# thesis.net
KiCad netlist of a schematic drawn in EAGLE
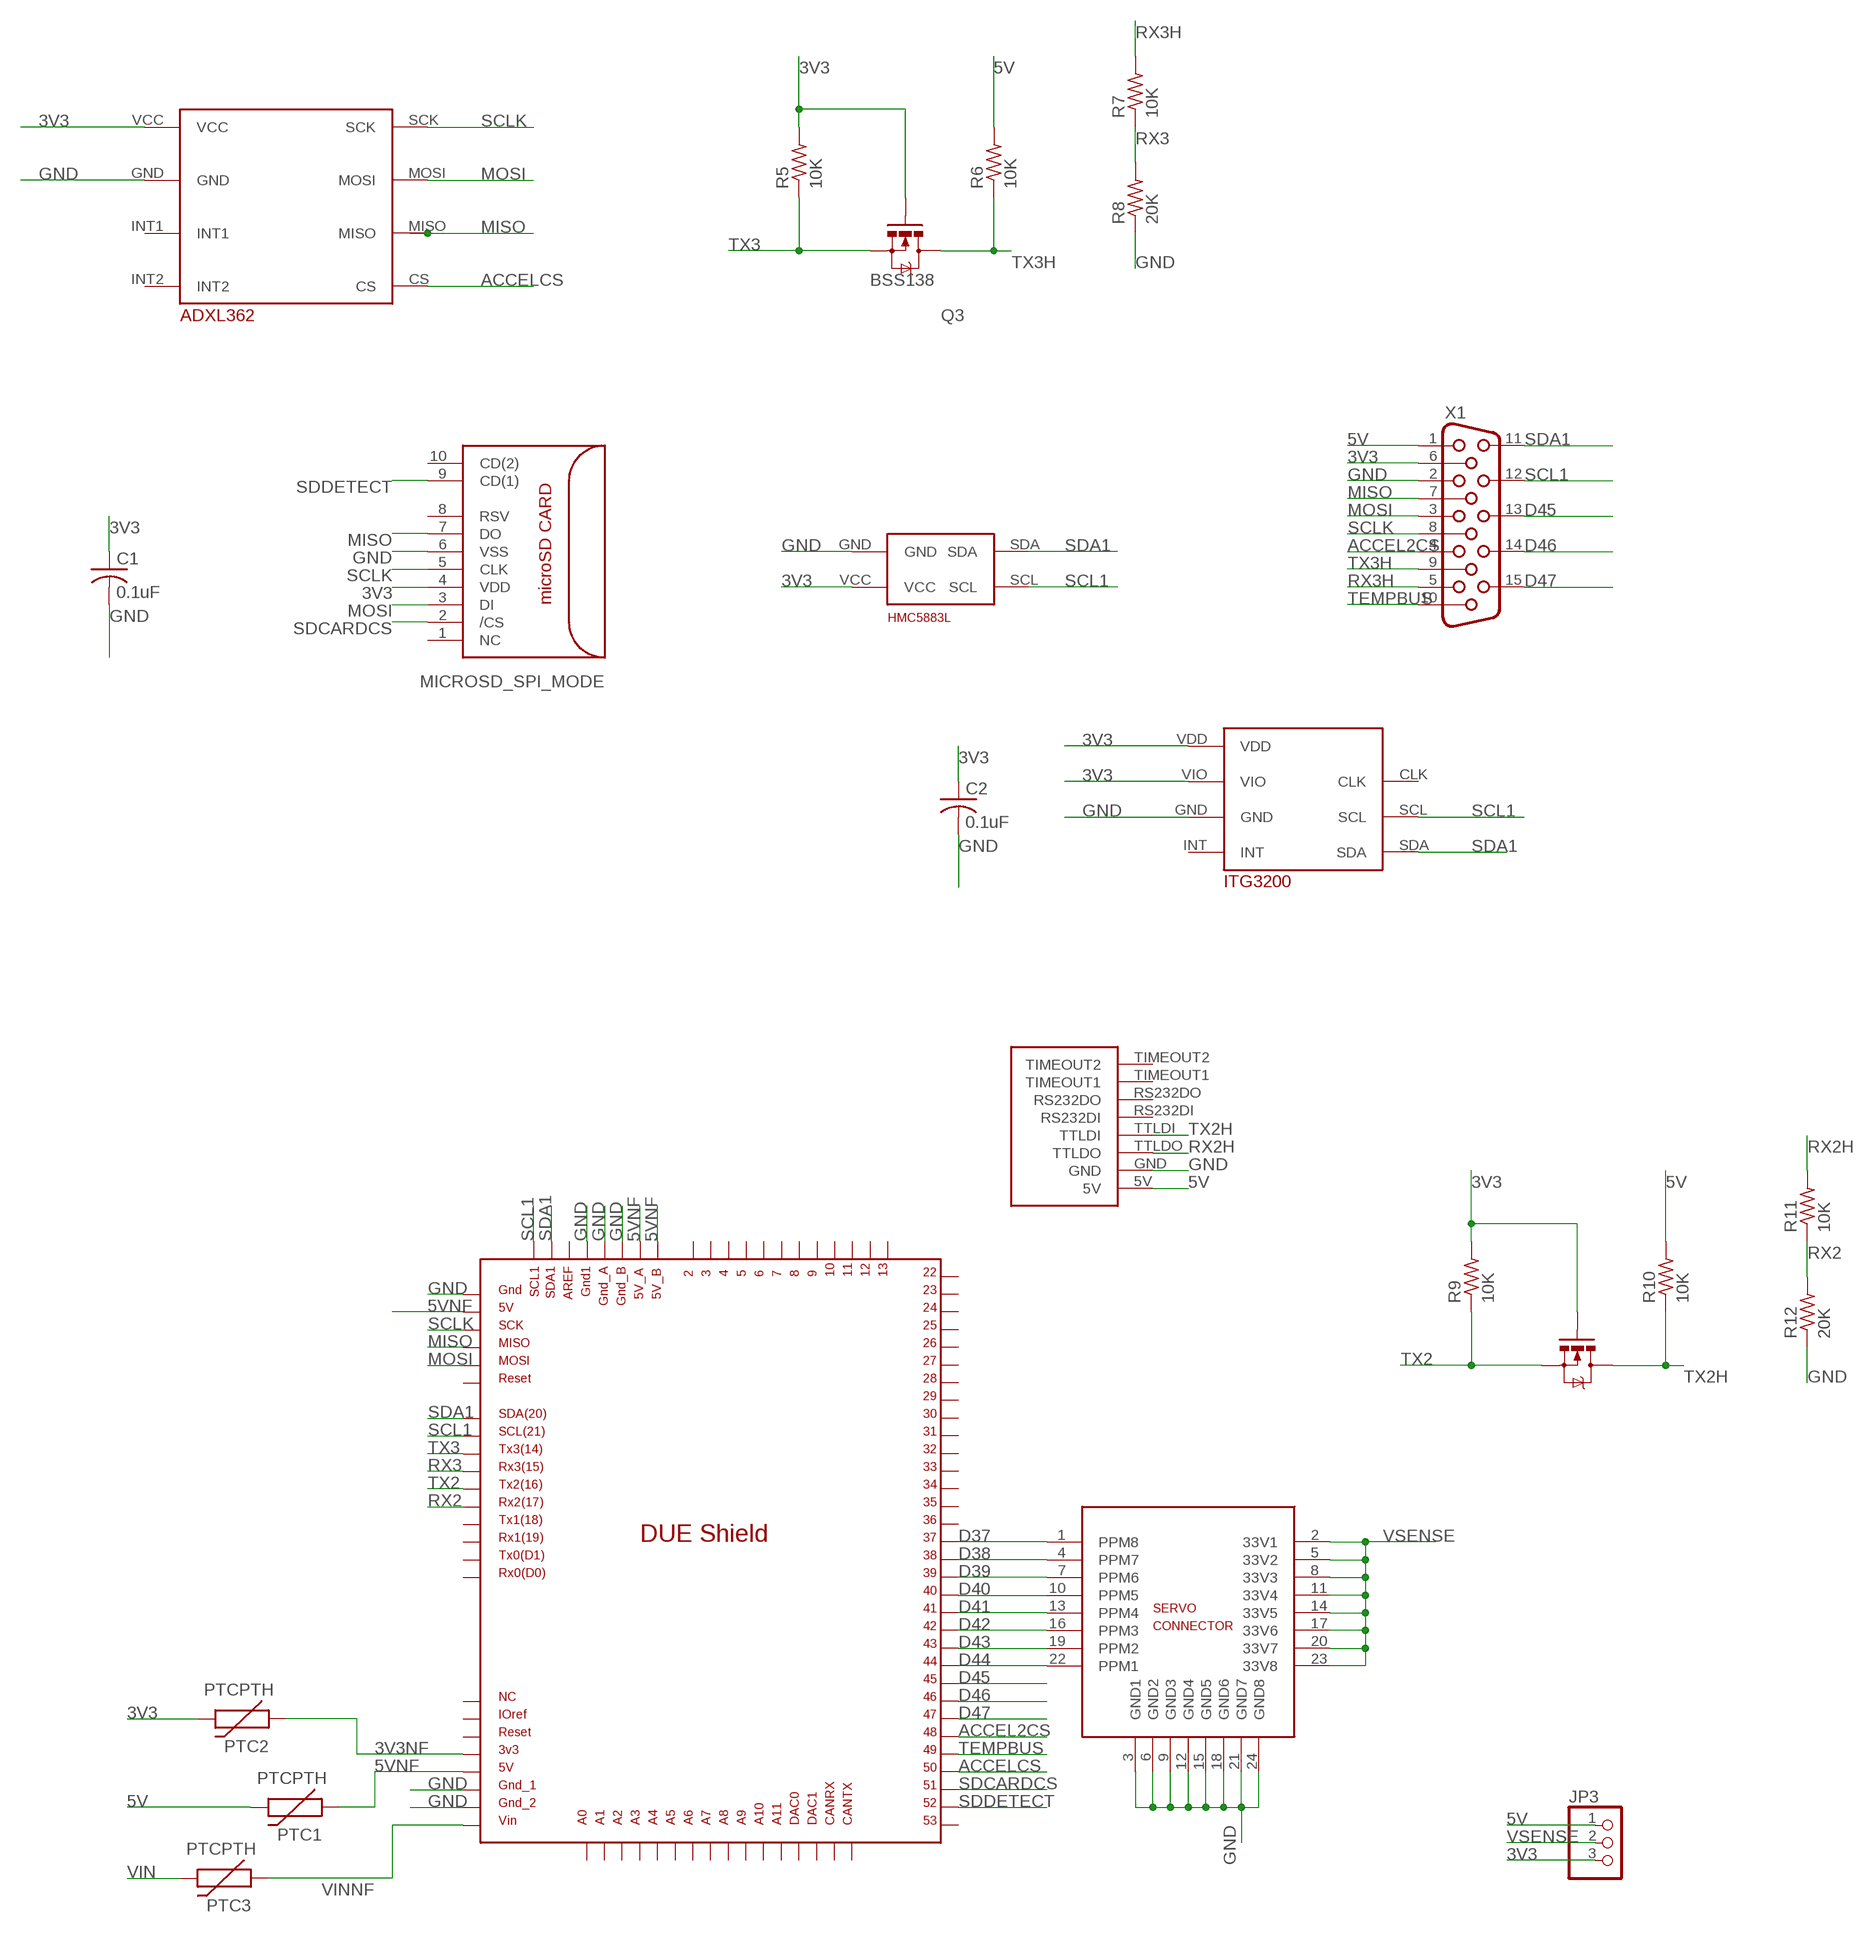
[diagram p0: schematic, sheet 1]

(export (version "E")
  (design (tool "Eeschema 10.0.6"))
  (components
    (comp (ref "C1")
      (value "0.1uF")
      (footprint "eagle-import:C0603")
      (libsource (lib "eagle-import") (part "C-USC0603"))
    )
    (comp (ref "C2")
      (value "0.1uF")
      (footprint "eagle-import:C0603")
      (libsource (lib "eagle-import") (part "C-USC0603"))
    )
    (comp (ref "JP3")
      (value "PINHD-1X3")
      (footprint "eagle-import:1X03")
      (libsource (lib "eagle-import") (part "PINHD-1X3"))
    )
    (comp (ref "PTC1")
      (value "PTCPTH")
      (footprint "eagle-import:PTC")
      (libsource (lib "eagle-import") (part "PTCPTH"))
    )
    (comp (ref "PTC2")
      (value "PTCPTH")
      (footprint "eagle-import:PTC")
      (libsource (lib "eagle-import") (part "PTCPTH"))
    )
    (comp (ref "PTC3")
      (value "PTCPTH")
      (footprint "eagle-import:PTC")
      (libsource (lib "eagle-import") (part "PTCPTH"))
    )
    (comp (ref "Q1")
      (value "BSS138")
      (footprint "eagle-import:SOT23")
      (libsource (lib "eagle-import") (part "MOSFET-NCHANNELBSS123LT1G"))
    )
    (comp (ref "Q3")
      (value "BSS138")
      (footprint "eagle-import:SOT23")
      (libsource (lib "eagle-import") (part "MOSFET-NCHANNELBSS123LT1G"))
    )
    (comp (ref "R5")
      (value "10K")
      (footprint "eagle-import:R0603")
      (libsource (lib "eagle-import") (part "R-US_R0603"))
    )
    (comp (ref "R6")
      (value "10K")
      (footprint "eagle-import:R0603")
      (libsource (lib "eagle-import") (part "R-US_R0603"))
    )
    (comp (ref "R7")
      (value "10K")
      (footprint "eagle-import:R0603")
      (libsource (lib "eagle-import") (part "R-US_R0603"))
    )
    (comp (ref "R8")
      (value "20K")
      (footprint "eagle-import:R0603")
      (libsource (lib "eagle-import") (part "R-US_R0603"))
    )
    (comp (ref "R9")
      (value "10K")
      (footprint "eagle-import:R0603")
      (libsource (lib "eagle-import") (part "R-US_R0603"))
    )
    (comp (ref "R10")
      (value "10K")
      (footprint "eagle-import:R0603")
      (libsource (lib "eagle-import") (part "R-US_R0603"))
    )
    (comp (ref "R11")
      (value "10K")
      (footprint "eagle-import:R0603")
      (libsource (lib "eagle-import") (part "R-US_R0603"))
    )
    (comp (ref "R12")
      (value "20K")
      (footprint "eagle-import:R0603")
      (libsource (lib "eagle-import") (part "R-US_R0603"))
    )
    (comp (ref "U$1")
      (value "DUE(NORMAL)")
      (footprint "eagle-import:DUE(NORMAL)")
      (libsource (lib "eagle-import") (part "DUE(NORMAL)"))
    )
    (comp (ref "U$2")
      (value "MICROSD_SPI_MODE")
      (footprint "eagle-import:MICRO_SD_CONNECTOR")
      (libsource (lib "eagle-import") (part "MICROSD_SPI_MODE"))
    )
    (comp (ref "U$4")
      (value "HMC5883L")
      (footprint "eagle-import:HMC5883L")
      (libsource (lib "eagle-import") (part "HMC5883L"))
    )
    (comp (ref "U$5")
      (value "HEADER-3X8SERVO")
      (footprint "eagle-import:3X8RA")
      (libsource (lib "eagle-import") (part "HEADER-3X8SERVO"))
    )
    (comp (ref "U$6")
      (value "UBLOXLEA6TBOB")
      (footprint "eagle-import:UBLOXLEA6TBOB")
      (libsource (lib "eagle-import") (part "UBLOXLEA6TBOB"))
    )
    (comp (ref "U$7")
      (value "ITG3200")
      (footprint "eagle-import:ITG3200")
      (libsource (lib "eagle-import") (part "ITG3200"))
    )
    (comp (ref "U$8")
      (value "ADXL362")
      (footprint "eagle-import:ADXL362")
      (libsource (lib "eagle-import") (part "ADXL362"))
    )
    (comp (ref "X1")
      (value "HF15V")
      (footprint "eagle-import:HDF15V")
      (libsource (lib "eagle-import") (part "HF15V"))
    )
  )
  (nets
    (net (code "1") (name "/3V3") (class "Default")
      (node (ref "C1") (pin "1") (pinfunction "1_1") (pintype "passive"))
      (node (ref "C2") (pin "1") (pinfunction "1_1") (pintype "passive"))
      (node (ref "JP3") (pin "3") (pinfunction "3_3") (pintype "passive"))
      (node (ref "PTC2") (pin "P$2") (pinfunction "2_P$2") (pintype "bidirectional"))
      (node (ref "Q1") (pin "1") (pinfunction "G_1") (pintype "passive"))
      (node (ref "Q3") (pin "1") (pinfunction "G_1") (pintype "passive"))
      (node (ref "R5") (pin "2") (pinfunction "2_2") (pintype "passive"))
      (node (ref "R9") (pin "2") (pinfunction "2_2") (pintype "passive"))
      (node (ref "U$2") (pin "4") (pinfunction "VDD_4") (pintype "bidirectional"))
      (node (ref "U$4") (pin "VCC") (pinfunction "VCC_VCC") (pintype "bidirectional"))
      (node (ref "U$7") (pin "VDD") (pinfunction "VDD_VDD") (pintype "bidirectional"))
      (node (ref "U$7") (pin "VIO") (pinfunction "VIO_VIO") (pintype "bidirectional"))
      (node (ref "U$8") (pin "VCC") (pinfunction "VCC_VCC") (pintype "bidirectional"))
      (node (ref "X1") (pin "6") (pinfunction "6_6") (pintype "passive"))
    )
    (net (code "2") (name "/3V3NF") (class "Default")
      (node (ref "PTC2") (pin "P$1") (pinfunction "1_P$1") (pintype "bidirectional"))
      (node (ref "U$1") (pin "3V3") (pinfunction "3V3_3V3") (pintype "bidirectional"))
    )
    (net (code "3") (name "/5V") (class "Default")
      (node (ref "JP3") (pin "1") (pinfunction "1_1") (pintype "passive"))
      (node (ref "PTC1") (pin "P$2") (pinfunction "2_P$2") (pintype "bidirectional"))
      (node (ref "R10") (pin "2") (pinfunction "2_2") (pintype "passive"))
      (node (ref "R6") (pin "2") (pinfunction "2_2") (pintype "passive"))
      (node (ref "U$6") (pin "5V") (pinfunction "5V_5V") (pintype "bidirectional"))
      (node (ref "X1") (pin "1") (pinfunction "1_1") (pintype "passive"))
    )
    (net (code "4") (name "/5VNF") (class "Default")
      (node (ref "PTC1") (pin "P$1") (pinfunction "1_P$1") (pintype "bidirectional"))
      (node (ref "U$1") (pin "5V") (pinfunction "5V_5V") (pintype "bidirectional"))
      (node (ref "U$1") (pin "5V_A") (pinfunction "5V_A_5V_A") (pintype "bidirectional"))
      (node (ref "U$1") (pin "5V_B") (pinfunction "5V_B_5V_B") (pintype "bidirectional"))
      (node (ref "U$1") (pin "GND_ICSP") (pinfunction "GND_ICSP_GND_ICSP") (pintype "bidirectional"))
    )
    (net (code "5") (name "/ACCEL2CS") (class "Default")
      (node (ref "U$1") (pin "48") (pinfunction "48_48") (pintype "bidirectional"))
      (node (ref "X1") (pin "4") (pinfunction "4_4") (pintype "passive"))
    )
    (net (code "6") (name "/ACCELCS") (class "Default")
      (node (ref "U$1") (pin "50") (pinfunction "50_50") (pintype "bidirectional"))
      (node (ref "U$8") (pin "CS") (pinfunction "CS_CS") (pintype "bidirectional"))
    )
    (net (code "7") (name "/D37") (class "Default")
      (node (ref "U$1") (pin "37") (pinfunction "37_37") (pintype "bidirectional"))
      (node (ref "U$5") (pin "1") (pinfunction "PPM8_1") (pintype "bidirectional"))
    )
    (net (code "8") (name "/D38") (class "Default")
      (node (ref "U$1") (pin "38") (pinfunction "38_38") (pintype "bidirectional"))
      (node (ref "U$5") (pin "4") (pinfunction "PPM7_4") (pintype "bidirectional"))
    )
    (net (code "9") (name "/D39") (class "Default")
      (node (ref "U$1") (pin "39") (pinfunction "39_39") (pintype "bidirectional"))
      (node (ref "U$5") (pin "7") (pinfunction "PPM6_7") (pintype "bidirectional"))
    )
    (net (code "10") (name "/D40") (class "Default")
      (node (ref "U$1") (pin "40") (pinfunction "40_40") (pintype "bidirectional"))
      (node (ref "U$5") (pin "10") (pinfunction "PPM5_10") (pintype "bidirectional"))
    )
    (net (code "11") (name "/D41") (class "Default")
      (node (ref "U$1") (pin "41") (pinfunction "41_41") (pintype "bidirectional"))
      (node (ref "U$5") (pin "13") (pinfunction "PPM4_13") (pintype "bidirectional"))
    )
    (net (code "12") (name "/D42") (class "Default")
      (node (ref "U$1") (pin "42") (pinfunction "42_42") (pintype "bidirectional"))
      (node (ref "U$5") (pin "16") (pinfunction "PPM3_16") (pintype "bidirectional"))
    )
    (net (code "13") (name "/D43") (class "Default")
      (node (ref "U$1") (pin "43") (pinfunction "43_43") (pintype "bidirectional"))
      (node (ref "U$5") (pin "19") (pinfunction "PPM2_19") (pintype "bidirectional"))
    )
    (net (code "14") (name "/D44") (class "Default")
      (node (ref "U$1") (pin "44") (pinfunction "44_44") (pintype "bidirectional"))
      (node (ref "U$5") (pin "22") (pinfunction "PPM1_22") (pintype "bidirectional"))
    )
    (net (code "15") (name "/D45") (class "Default")
      (node (ref "U$1") (pin "45") (pinfunction "45_45") (pintype "bidirectional"))
      (node (ref "X1") (pin "13") (pinfunction "13_13") (pintype "passive"))
    )
    (net (code "16") (name "/D46") (class "Default")
      (node (ref "U$1") (pin "46") (pinfunction "46_46") (pintype "bidirectional"))
      (node (ref "X1") (pin "14") (pinfunction "14_14") (pintype "passive"))
    )
    (net (code "17") (name "/D47") (class "Default")
      (node (ref "U$1") (pin "47") (pinfunction "47_47") (pintype "bidirectional"))
      (node (ref "X1") (pin "15") (pinfunction "15_15") (pintype "passive"))
    )
    (net (code "18") (name "/GND") (class "Default")
      (node (ref "C1") (pin "2") (pinfunction "2_2") (pintype "passive"))
      (node (ref "C2") (pin "2") (pinfunction "2_2") (pintype "passive"))
      (node (ref "R12") (pin "1") (pinfunction "1_1") (pintype "passive"))
      (node (ref "R8") (pin "1") (pinfunction "1_1") (pintype "passive"))
      (node (ref "U$1") (pin "5V_ICSP") (pinfunction "5V_ICSP_5V_ICSP") (pintype "bidirectional"))
      (node (ref "U$1") (pin "GND1") (pinfunction "GND1_GND1") (pintype "bidirectional"))
      (node (ref "U$1") (pin "GND_1") (pinfunction "GND_1_GND_1") (pintype "bidirectional"))
      (node (ref "U$1") (pin "GND_2") (pinfunction "GND_2_GND_2") (pintype "bidirectional"))
      (node (ref "U$1") (pin "GND_A") (pinfunction "GND_A_GND_A") (pintype "bidirectional"))
      (node (ref "U$1") (pin "GND_B") (pinfunction "GND_B_GND_B") (pintype "bidirectional"))
      (node (ref "U$2") (pin "6") (pinfunction "VSS_6") (pintype "bidirectional"))
      (node (ref "U$4") (pin "GND") (pinfunction "GND_GND") (pintype "bidirectional"))
      (node (ref "U$5") (pin "12") (pinfunction "GND4_12") (pintype "bidirectional"))
      (node (ref "U$5") (pin "15") (pinfunction "GND5_15") (pintype "bidirectional"))
      (node (ref "U$5") (pin "18") (pinfunction "GND6_18") (pintype "bidirectional"))
      (node (ref "U$5") (pin "21") (pinfunction "GND7_21") (pintype "bidirectional"))
      (node (ref "U$5") (pin "24") (pinfunction "GND8_24") (pintype "bidirectional"))
      (node (ref "U$5") (pin "3") (pinfunction "GND1_3") (pintype "bidirectional"))
      (node (ref "U$5") (pin "6") (pinfunction "GND2_6") (pintype "bidirectional"))
      (node (ref "U$5") (pin "9") (pinfunction "GND3_9") (pintype "bidirectional"))
      (node (ref "U$6") (pin "GND") (pinfunction "GND_GND") (pintype "bidirectional"))
      (node (ref "U$7") (pin "GND") (pinfunction "GND_GND") (pintype "bidirectional"))
      (node (ref "U$8") (pin "GND") (pinfunction "GND_GND") (pintype "bidirectional"))
      (node (ref "X1") (pin "2") (pinfunction "2_2") (pintype "passive"))
    )
    (net (code "19") (name "/MISO") (class "Default")
      (node (ref "U$1") (pin "MISO_ICSP") (pinfunction "MISO_ICSP_MISO_ICSP") (pintype "bidirectional"))
      (node (ref "U$2") (pin "7") (pinfunction "DO_7") (pintype "bidirectional"))
      (node (ref "U$8") (pin "MISO") (pinfunction "MISO_MISO") (pintype "bidirectional"))
      (node (ref "X1") (pin "7") (pinfunction "7_7") (pintype "passive"))
    )
    (net (code "20") (name "/MOSI") (class "Default")
      (node (ref "U$1") (pin "MOSI_ICSP") (pinfunction "MOSI_ICSP_MOSI_ICSP") (pintype "bidirectional"))
      (node (ref "U$2") (pin "3") (pinfunction "DI_3") (pintype "bidirectional"))
      (node (ref "U$8") (pin "MOSI") (pinfunction "MOSI_MOSI") (pintype "bidirectional"))
      (node (ref "X1") (pin "3") (pinfunction "3_3") (pintype "passive"))
    )
    (net (code "21") (name "/RX2") (class "Default")
      (node (ref "R11") (pin "1") (pinfunction "1_1") (pintype "passive"))
      (node (ref "R12") (pin "2") (pinfunction "2_2") (pintype "passive"))
      (node (ref "U$1") (pin "RX2") (pinfunction "RX2_RX2") (pintype "bidirectional"))
    )
    (net (code "22") (name "/RX2H") (class "Default")
      (node (ref "R11") (pin "2") (pinfunction "2_2") (pintype "passive"))
      (node (ref "U$6") (pin "TTLDO") (pinfunction "TTLDO_TTLDO") (pintype "bidirectional"))
    )
    (net (code "23") (name "/RX3") (class "Default")
      (node (ref "R7") (pin "1") (pinfunction "1_1") (pintype "passive"))
      (node (ref "R8") (pin "2") (pinfunction "2_2") (pintype "passive"))
      (node (ref "U$1") (pin "RX3") (pinfunction "RX3_RX3") (pintype "bidirectional"))
    )
    (net (code "24") (name "/RX3H") (class "Default")
      (node (ref "R7") (pin "2") (pinfunction "2_2") (pintype "passive"))
      (node (ref "X1") (pin "5") (pinfunction "5_5") (pintype "passive"))
    )
    (net (code "25") (name "/SCL1") (class "Default")
      (node (ref "U$1") (pin "SCL") (pinfunction "SCL_SCL") (pintype "bidirectional"))
      (node (ref "U$1") (pin "SCL1") (pinfunction "SCL1_SCL1") (pintype "bidirectional"))
      (node (ref "U$4") (pin "SCL") (pinfunction "SCL_SCL") (pintype "bidirectional"))
      (node (ref "U$7") (pin "SCL") (pinfunction "SCL_SCL") (pintype "bidirectional"))
      (node (ref "X1") (pin "12") (pinfunction "12_12") (pintype "passive"))
    )
    (net (code "26") (name "/SCLK") (class "Default")
      (node (ref "U$1") (pin "SCK_ICSP") (pinfunction "SCK_ICSP_SCK_ICSP") (pintype "bidirectional"))
      (node (ref "U$2") (pin "5") (pinfunction "CLK_5") (pintype "bidirectional"))
      (node (ref "U$8") (pin "SCK") (pinfunction "SCK_SCK") (pintype "bidirectional"))
      (node (ref "X1") (pin "8") (pinfunction "8_8") (pintype "passive"))
    )
    (net (code "27") (name "/SDA1") (class "Default")
      (node (ref "U$1") (pin "SDA") (pinfunction "SDA_SDA") (pintype "bidirectional"))
      (node (ref "U$1") (pin "SDA1") (pinfunction "SDA1_SDA1") (pintype "bidirectional"))
      (node (ref "U$4") (pin "SDA") (pinfunction "SDA_SDA") (pintype "bidirectional"))
      (node (ref "U$7") (pin "SDA") (pinfunction "SDA_SDA") (pintype "bidirectional"))
      (node (ref "X1") (pin "11") (pinfunction "11_11") (pintype "passive"))
    )
    (net (code "28") (name "/SDCARDCS") (class "Default")
      (node (ref "U$1") (pin "51") (pinfunction "51_51") (pintype "bidirectional"))
      (node (ref "U$2") (pin "2") (pinfunction "/CS_2") (pintype "bidirectional"))
    )
    (net (code "29") (name "/SDDETECT") (class "Default")
      (node (ref "U$1") (pin "52") (pinfunction "52_52") (pintype "bidirectional"))
      (node (ref "U$2") (pin "9") (pinfunction "CD(1)_9") (pintype "bidirectional"))
    )
    (net (code "30") (name "/TEMPBUS") (class "Default")
      (node (ref "U$1") (pin "49") (pinfunction "49_49") (pintype "bidirectional"))
      (node (ref "X1") (pin "10") (pinfunction "10_10") (pintype "passive"))
    )
    (net (code "31") (name "/TX2") (class "Default")
      (node (ref "Q1") (pin "2") (pinfunction "S_2") (pintype "passive"))
      (node (ref "R9") (pin "1") (pinfunction "1_1") (pintype "passive"))
      (node (ref "U$1") (pin "TX2") (pinfunction "TX2_TX2") (pintype "bidirectional"))
    )
    (net (code "32") (name "/TX2H") (class "Default")
      (node (ref "Q1") (pin "3") (pinfunction "D_3") (pintype "passive"))
      (node (ref "R10") (pin "1") (pinfunction "1_1") (pintype "passive"))
      (node (ref "U$6") (pin "TTLDI") (pinfunction "TTLDI_TTLDI") (pintype "bidirectional"))
    )
    (net (code "33") (name "/TX3") (class "Default")
      (node (ref "Q3") (pin "2") (pinfunction "S_2") (pintype "passive"))
      (node (ref "R5") (pin "1") (pinfunction "1_1") (pintype "passive"))
      (node (ref "U$1") (pin "TX3") (pinfunction "TX3_TX3") (pintype "bidirectional"))
    )
    (net (code "34") (name "/TX3H") (class "Default")
      (node (ref "Q3") (pin "3") (pinfunction "D_3") (pintype "passive"))
      (node (ref "R6") (pin "1") (pinfunction "1_1") (pintype "passive"))
      (node (ref "X1") (pin "9") (pinfunction "9_9") (pintype "passive"))
    )
    (net (code "35") (name "/VIN") (class "Default")
      (node (ref "PTC3") (pin "P$2") (pinfunction "2_P$2") (pintype "bidirectional"))
    )
    (net (code "36") (name "/VINNF") (class "Default")
      (node (ref "PTC3") (pin "P$1") (pinfunction "1_P$1") (pintype "bidirectional"))
      (node (ref "U$1") (pin "VIN") (pinfunction "VIN_VIN") (pintype "bidirectional"))
    )
    (net (code "37") (name "/VSENSE") (class "Default")
      (node (ref "JP3") (pin "2") (pinfunction "2_2") (pintype "passive"))
      (node (ref "U$5") (pin "11") (pinfunction "33V4_11") (pintype "bidirectional"))
      (node (ref "U$5") (pin "14") (pinfunction "33V5_14") (pintype "bidirectional"))
      (node (ref "U$5") (pin "17") (pinfunction "33V6_17") (pintype "bidirectional"))
      (node (ref "U$5") (pin "2") (pinfunction "33V1_2") (pintype "bidirectional"))
      (node (ref "U$5") (pin "20") (pinfunction "33V7_20") (pintype "bidirectional"))
      (node (ref "U$5") (pin "23") (pinfunction "33V8_23") (pintype "bidirectional"))
      (node (ref "U$5") (pin "5") (pinfunction "33V2_5") (pintype "bidirectional"))
      (node (ref "U$5") (pin "8") (pinfunction "33V3_8") (pintype "bidirectional"))
    )
    (net (code "38") (name "unconnected-(U$1-Pad2)") (class "Default")
      (node (ref "U$1") (pin "2") (pinfunction "2_2") (pintype "bidirectional"))
    )
    (net (code "39") (name "unconnected-(U$1-Pad3)") (class "Default")
      (node (ref "U$1") (pin "3") (pinfunction "3_3") (pintype "bidirectional"))
    )
    (net (code "40") (name "unconnected-(U$1-Pad4)") (class "Default")
      (node (ref "U$1") (pin "4") (pinfunction "4_4") (pintype "bidirectional"))
    )
    (net (code "41") (name "unconnected-(U$1-Pad5)") (class "Default")
      (node (ref "U$1") (pin "5") (pinfunction "5_5") (pintype "bidirectional"))
    )
    (net (code "42") (name "unconnected-(U$1-Pad6)") (class "Default")
      (node (ref "U$1") (pin "6") (pinfunction "6_6") (pintype "bidirectional"))
    )
    (net (code "43") (name "unconnected-(U$1-Pad7)") (class "Default")
      (node (ref "U$1") (pin "7") (pinfunction "7_7") (pintype "bidirectional"))
    )
    (net (code "44") (name "unconnected-(U$1-Pad8)") (class "Default")
      (node (ref "U$1") (pin "8") (pinfunction "8_8") (pintype "bidirectional"))
    )
    (net (code "45") (name "unconnected-(U$1-Pad9)") (class "Default")
      (node (ref "U$1") (pin "9") (pinfunction "9_9") (pintype "bidirectional"))
    )
    (net (code "46") (name "unconnected-(U$1-Pad10)") (class "Default")
      (node (ref "U$1") (pin "10") (pinfunction "10_10") (pintype "bidirectional"))
    )
    (net (code "47") (name "unconnected-(U$1-Pad11)") (class "Default")
      (node (ref "U$1") (pin "11") (pinfunction "11_11") (pintype "bidirectional"))
    )
    (net (code "48") (name "unconnected-(U$1-Pad12)") (class "Default")
      (node (ref "U$1") (pin "12") (pinfunction "12_12") (pintype "bidirectional"))
    )
    (net (code "49") (name "unconnected-(U$1-Pad13)") (class "Default")
      (node (ref "U$1") (pin "13") (pinfunction "13_13") (pintype "bidirectional"))
    )
    (net (code "50") (name "unconnected-(U$1-Pad22)") (class "Default")
      (node (ref "U$1") (pin "22") (pinfunction "22_22") (pintype "bidirectional"))
    )
    (net (code "51") (name "unconnected-(U$1-Pad23)") (class "Default")
      (node (ref "U$1") (pin "23") (pinfunction "23_23") (pintype "bidirectional"))
    )
    (net (code "52") (name "unconnected-(U$1-Pad24)") (class "Default")
      (node (ref "U$1") (pin "24") (pinfunction "24_24") (pintype "bidirectional"))
    )
    (net (code "53") (name "unconnected-(U$1-Pad25)") (class "Default")
      (node (ref "U$1") (pin "25") (pinfunction "25_25") (pintype "bidirectional"))
    )
    (net (code "54") (name "unconnected-(U$1-Pad26)") (class "Default")
      (node (ref "U$1") (pin "26") (pinfunction "26_26") (pintype "bidirectional"))
    )
    (net (code "55") (name "unconnected-(U$1-Pad27)") (class "Default")
      (node (ref "U$1") (pin "27") (pinfunction "27_27") (pintype "bidirectional"))
    )
    (net (code "56") (name "unconnected-(U$1-Pad28)") (class "Default")
      (node (ref "U$1") (pin "28") (pinfunction "28_28") (pintype "bidirectional"))
    )
    (net (code "57") (name "unconnected-(U$1-Pad29)") (class "Default")
      (node (ref "U$1") (pin "29") (pinfunction "29_29") (pintype "bidirectional"))
    )
    (net (code "58") (name "unconnected-(U$1-Pad30)") (class "Default")
      (node (ref "U$1") (pin "30") (pinfunction "30_30") (pintype "bidirectional"))
    )
    (net (code "59") (name "unconnected-(U$1-Pad31)") (class "Default")
      (node (ref "U$1") (pin "31") (pinfunction "31_31") (pintype "bidirectional"))
    )
    (net (code "60") (name "unconnected-(U$1-Pad32)") (class "Default")
      (node (ref "U$1") (pin "32") (pinfunction "32_32") (pintype "bidirectional"))
    )
    (net (code "61") (name "unconnected-(U$1-Pad33)") (class "Default")
      (node (ref "U$1") (pin "33") (pinfunction "33_33") (pintype "bidirectional"))
    )
    (net (code "62") (name "unconnected-(U$1-Pad34)") (class "Default")
      (node (ref "U$1") (pin "34") (pinfunction "34_34") (pintype "bidirectional"))
    )
    (net (code "63") (name "unconnected-(U$1-Pad35)") (class "Default")
      (node (ref "U$1") (pin "35") (pinfunction "35_35") (pintype "bidirectional"))
    )
    (net (code "64") (name "unconnected-(U$1-Pad36)") (class "Default")
      (node (ref "U$1") (pin "36") (pinfunction "36_36") (pintype "bidirectional"))
    )
    (net (code "65") (name "unconnected-(U$1-Pad53)") (class "Default")
      (node (ref "U$1") (pin "53") (pinfunction "53_53") (pintype "bidirectional"))
    )
    (net (code "66") (name "unconnected-(U$1-PadA0)") (class "Default")
      (node (ref "U$1") (pin "A0") (pinfunction "A0_A0") (pintype "bidirectional"))
    )
    (net (code "67") (name "unconnected-(U$1-PadA1)") (class "Default")
      (node (ref "U$1") (pin "A1") (pinfunction "A1_A1") (pintype "bidirectional"))
    )
    (net (code "68") (name "unconnected-(U$1-PadA2)") (class "Default")
      (node (ref "U$1") (pin "A2") (pinfunction "A2_A2") (pintype "bidirectional"))
    )
    (net (code "69") (name "unconnected-(U$1-PadA3)") (class "Default")
      (node (ref "U$1") (pin "A3") (pinfunction "A3_A3") (pintype "bidirectional"))
    )
    (net (code "70") (name "unconnected-(U$1-PadA4)") (class "Default")
      (node (ref "U$1") (pin "A4") (pinfunction "A4_A4") (pintype "bidirectional"))
    )
    (net (code "71") (name "unconnected-(U$1-PadA5)") (class "Default")
      (node (ref "U$1") (pin "A5") (pinfunction "A5_A5") (pintype "bidirectional"))
    )
    (net (code "72") (name "unconnected-(U$1-PadA6)") (class "Default")
      (node (ref "U$1") (pin "A6") (pinfunction "A6_A6") (pintype "bidirectional"))
    )
    (net (code "73") (name "unconnected-(U$1-PadA7)") (class "Default")
      (node (ref "U$1") (pin "A7") (pinfunction "A7_A7") (pintype "bidirectional"))
    )
    (net (code "74") (name "unconnected-(U$1-PadA8)") (class "Default")
      (node (ref "U$1") (pin "A8") (pinfunction "A8_A8") (pintype "bidirectional"))
    )
    (net (code "75") (name "unconnected-(U$1-PadA9)") (class "Default")
      (node (ref "U$1") (pin "A9") (pinfunction "A9_A9") (pintype "bidirectional"))
    )
    (net (code "76") (name "unconnected-(U$1-PadA10)") (class "Default")
      (node (ref "U$1") (pin "A10") (pinfunction "A10_A10") (pintype "bidirectional"))
    )
    (net (code "77") (name "unconnected-(U$1-PadA11)") (class "Default")
      (node (ref "U$1") (pin "A11") (pinfunction "A11_A11") (pintype "bidirectional"))
    )
    (net (code "78") (name "unconnected-(U$1-PadAREF)") (class "Default")
      (node (ref "U$1") (pin "AREF") (pinfunction "AREF_AREF") (pintype "bidirectional"))
    )
    (net (code "79") (name "unconnected-(U$1-PadCANRX)") (class "Default")
      (node (ref "U$1") (pin "CANRX") (pinfunction "CANRX_CANRX") (pintype "bidirectional"))
    )
    (net (code "80") (name "unconnected-(U$1-PadCANTX)") (class "Default")
      (node (ref "U$1") (pin "CANTX") (pinfunction "CANTX_CANTX") (pintype "bidirectional"))
    )
    (net (code "81") (name "unconnected-(U$1-PadDAC0)") (class "Default")
      (node (ref "U$1") (pin "DAC0") (pinfunction "DAC0_DAC0") (pintype "bidirectional"))
    )
    (net (code "82") (name "unconnected-(U$1-PadDAC1)") (class "Default")
      (node (ref "U$1") (pin "DAC1") (pinfunction "DAC1_DAC1") (pintype "bidirectional"))
    )
    (net (code "83") (name "unconnected-(U$1-PadIOREF)") (class "Default")
      (node (ref "U$1") (pin "IOREF") (pinfunction "IOREF_IOREF") (pintype "bidirectional"))
    )
    (net (code "84") (name "unconnected-(U$1-PadNC)") (class "Default")
      (node (ref "U$1") (pin "NC") (pinfunction "NC_NC") (pintype "bidirectional"))
    )
    (net (code "85") (name "unconnected-(U$1-PadRESET)") (class "Default")
      (node (ref "U$1") (pin "RESET") (pinfunction "RESET_RESET") (pintype "bidirectional"))
    )
    (net (code "86") (name "unconnected-(U$1-PadRESET_ICSP)") (class "Default")
      (node (ref "U$1") (pin "RESET_ICSP") (pinfunction "RESET_ICSP_RESET_ICSP") (pintype "bidirectional"))
    )
    (net (code "87") (name "unconnected-(U$1-PadRX0)") (class "Default")
      (node (ref "U$1") (pin "RX0") (pinfunction "RX0_RX0") (pintype "bidirectional"))
    )
    (net (code "88") (name "unconnected-(U$1-PadRX1)") (class "Default")
      (node (ref "U$1") (pin "RX1") (pinfunction "RX1_RX1") (pintype "bidirectional"))
    )
    (net (code "89") (name "unconnected-(U$1-PadTX0)") (class "Default")
      (node (ref "U$1") (pin "TX0") (pinfunction "TX0_TX0") (pintype "bidirectional"))
    )
    (net (code "90") (name "unconnected-(U$1-PadTX1)") (class "Default")
      (node (ref "U$1") (pin "TX1") (pinfunction "TX1_TX1") (pintype "bidirectional"))
    )
    (net (code "91") (name "unconnected-(U$2-CD(2)-Pad10)") (class "Default")
      (node (ref "U$2") (pin "10") (pinfunction "CD(2)_10") (pintype "bidirectional"))
    )
    (net (code "92") (name "unconnected-(U$2-NC-Pad1)") (class "Default")
      (node (ref "U$2") (pin "1") (pinfunction "NC_1") (pintype "bidirectional"))
    )
    (net (code "93") (name "unconnected-(U$2-RSV-Pad8)") (class "Default")
      (node (ref "U$2") (pin "8") (pinfunction "RSV_8") (pintype "bidirectional"))
    )
    (net (code "94") (name "unconnected-(U$6-PadRS232DI)") (class "Default")
      (node (ref "U$6") (pin "RS232DI") (pinfunction "RS232DI_RS232DI") (pintype "bidirectional"))
    )
    (net (code "95") (name "unconnected-(U$6-PadRS232DO)") (class "Default")
      (node (ref "U$6") (pin "RS232DO") (pinfunction "RS232DO_RS232DO") (pintype "bidirectional"))
    )
    (net (code "96") (name "unconnected-(U$6-PadTIMEOUT1)") (class "Default")
      (node (ref "U$6") (pin "TIMEOUT1") (pinfunction "TIMEOUT1_TIMEOUT1") (pintype "bidirectional"))
    )
    (net (code "97") (name "unconnected-(U$6-PadTIMEOUT2)") (class "Default")
      (node (ref "U$6") (pin "TIMEOUT2") (pinfunction "TIMEOUT2_TIMEOUT2") (pintype "bidirectional"))
    )
    (net (code "98") (name "unconnected-(U$7-PadCLK)") (class "Default")
      (node (ref "U$7") (pin "CLK") (pinfunction "CLK_CLK") (pintype "bidirectional"))
    )
    (net (code "99") (name "unconnected-(U$7-PadINT)") (class "Default")
      (node (ref "U$7") (pin "INT") (pinfunction "INT_INT") (pintype "bidirectional"))
    )
    (net (code "100") (name "unconnected-(U$8-PadINT1)") (class "Default")
      (node (ref "U$8") (pin "INT1") (pinfunction "INT1_INT1") (pintype "bidirectional"))
    )
    (net (code "101") (name "unconnected-(U$8-PadINT2)") (class "Default")
      (node (ref "U$8") (pin "INT2") (pinfunction "INT2_INT2") (pintype "bidirectional"))
    )
  )
)
